# Deneigus_BMS.net
KiCad netlist of a schematic drawn in Altium Designer
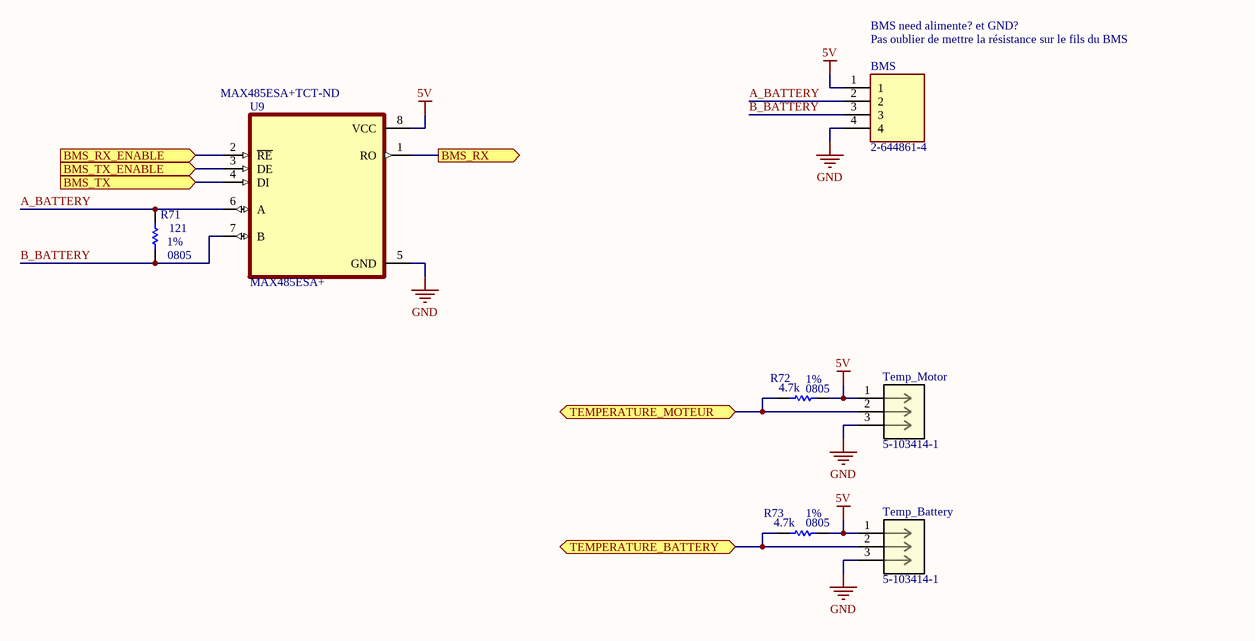
[diagram p0: Deneigus_BMS.SchDoc]

(export (version "E")
  (design (tool "Eeschema 10.0.6"))
  (components
    (comp (ref "BMS")
      (value "2-644861-4")
      (footprint "TE_2-644861-4:TE_2-644861-4")
      (description "Connector Header Through Hole 4 position 0.100 (2.54mm)")
      (fields (field (name "MF") "TE Connectivity"))
      (libsource (lib "2-644861-4") (part "2-644861-4"))
    )
    (comp (ref "R71")
      (value "121")
      (footprint "RES_0805")
      (description "RES - 0805")
      (fields
        (field (name "PACKAGE") "0805")
        (field (name "PRECISION") "1%")
        (field (name "CREATEDBY") "Jonathan Bouchard")
      )
      (libsource (lib "S7CAS_LIB2021") (part "RES - 0805"))
    )
    (comp (ref "R72")
      (value "4.7k")
      (footprint "RES_0805")
      (description "RES - 0805")
      (fields
        (field (name "PACKAGE") "0805")
        (field (name "PRECISION") "1%")
        (field (name "CREATEDBY") "Jonathan Bouchard")
      )
      (libsource (lib "S7CAS_LIB2021") (part "RES - 0805"))
    )
    (comp (ref "R73")
      (value "4.7k")
      (footprint "RES_0805")
      (description "RES - 0805")
      (fields
        (field (name "PACKAGE") "0805")
        (field (name "PRECISION") "1%")
        (field (name "CREATEDBY") "Jonathan Bouchard")
      )
      (libsource (lib "S7CAS_LIB2021") (part "RES - 0805"))
    )
    (comp (ref "Temp_Battery")
      (value "5-103414-1")
      (footprint "2021-04-13_19-21-58:CONN_5-103414-1_TYCO")
      (description "No Description Available")
      (fields (field (name "COPYRIGHT") "Copyright (C) 2016 Accelerated Designs. All rights reserved"))
      (libsource (lib "3pins") (part "5-103414-1"))
    )
    (comp (ref "Temp_Motor")
      (value "5-103414-1")
      (footprint "2021-04-13_19-21-58:CONN_5-103414-1_TYCO")
      (description "No Description Available")
      (fields (field (name "COPYRIGHT") "Copyright (C) 2016 Accelerated Designs. All rights reserved"))
      (libsource (lib "3pins") (part "5-103414-1"))
    )
    (comp (ref "U9")
      (value "MAX485ESA+")
      (footprint "SOIC127P600X175-8N")
      (description "1/1 Transceiver Half RS422, RS485 8-SOIC")
      (fields
        (field (name "MF") "Maxim Integrated")
        (field (name "SUPPLIER PART NUMBER 1") "MAX485ESA+TCT-ND")
      )
      (libsource (lib "MAX485ESA_") (part "MAX485ESA+"))
    )
  )
  (nets
    (net (code "1") (name "/A_BATTERY") (class "Default")
      (node (ref "BMS") (pin "2") (pinfunction "2_2") (pintype "passive"))
      (node (ref "R71") (pin "2") (pinfunction "2_2") (pintype "passive"))
      (node (ref "U9") (pin "6") (pinfunction "A_6") (pintype "bidirectional"))
    )
    (net (code "2") (name "/BMS_RX") (class "Default")
      (node (ref "U9") (pin "1") (pinfunction "RO_1") (pintype "output"))
    )
    (net (code "3") (name "/BMS_RX_ENABLE") (class "Default")
      (node (ref "U9") (pin "2") (pinfunction "~{RE}_2") (pintype "input"))
    )
    (net (code "4") (name "/BMS_TX") (class "Default")
      (node (ref "U9") (pin "4") (pinfunction "DI_4") (pintype "input"))
    )
    (net (code "5") (name "/BMS_TX_ENABLE") (class "Default")
      (node (ref "U9") (pin "3") (pinfunction "DE_3") (pintype "input"))
    )
    (net (code "6") (name "/B_BATTERY") (class "Default")
      (node (ref "BMS") (pin "3") (pinfunction "3_3") (pintype "passive"))
      (node (ref "R71") (pin "1") (pinfunction "1_1") (pintype "passive"))
      (node (ref "U9") (pin "7") (pinfunction "B_7") (pintype "bidirectional"))
    )
    (net (code "7") (name "/TEMPERATURE_BATTERY") (class "Default")
      (node (ref "R73") (pin "1") (pinfunction "1_1") (pintype "passive"))
      (node (ref "Temp_Battery") (pin "2") (pinfunction "2_2") (pintype "passive"))
    )
    (net (code "8") (name "/TEMPERATURE_MOTEUR") (class "Default")
      (node (ref "R72") (pin "1") (pinfunction "1_1") (pintype "passive"))
      (node (ref "Temp_Motor") (pin "2") (pinfunction "2_2") (pintype "passive"))
    )
    (net (code "9") (name "5V") (class "Default")
      (node (ref "BMS") (pin "1") (pinfunction "1_1") (pintype "passive"))
      (node (ref "R72") (pin "2") (pinfunction "2_2") (pintype "passive"))
      (node (ref "R73") (pin "2") (pinfunction "2_2") (pintype "passive"))
      (node (ref "Temp_Battery") (pin "1") (pinfunction "1_1") (pintype "passive"))
      (node (ref "Temp_Motor") (pin "1") (pinfunction "1_1") (pintype "passive"))
      (node (ref "U9") (pin "8") (pinfunction "VCC_8") (pintype "power_in"))
    )
    (net (code "10") (name "GND") (class "Default")
      (node (ref "BMS") (pin "4") (pinfunction "4_4") (pintype "passive"))
      (node (ref "Temp_Battery") (pin "3") (pinfunction "3_3") (pintype "passive"))
      (node (ref "Temp_Motor") (pin "3") (pinfunction "3_3") (pintype "passive"))
      (node (ref "U9") (pin "5") (pinfunction "GND_5") (pintype "power_in"))
    )
  )
)
